# 01-STM32F303VET6.net
KiCad netlist of a schematic drawn in Altium Designer
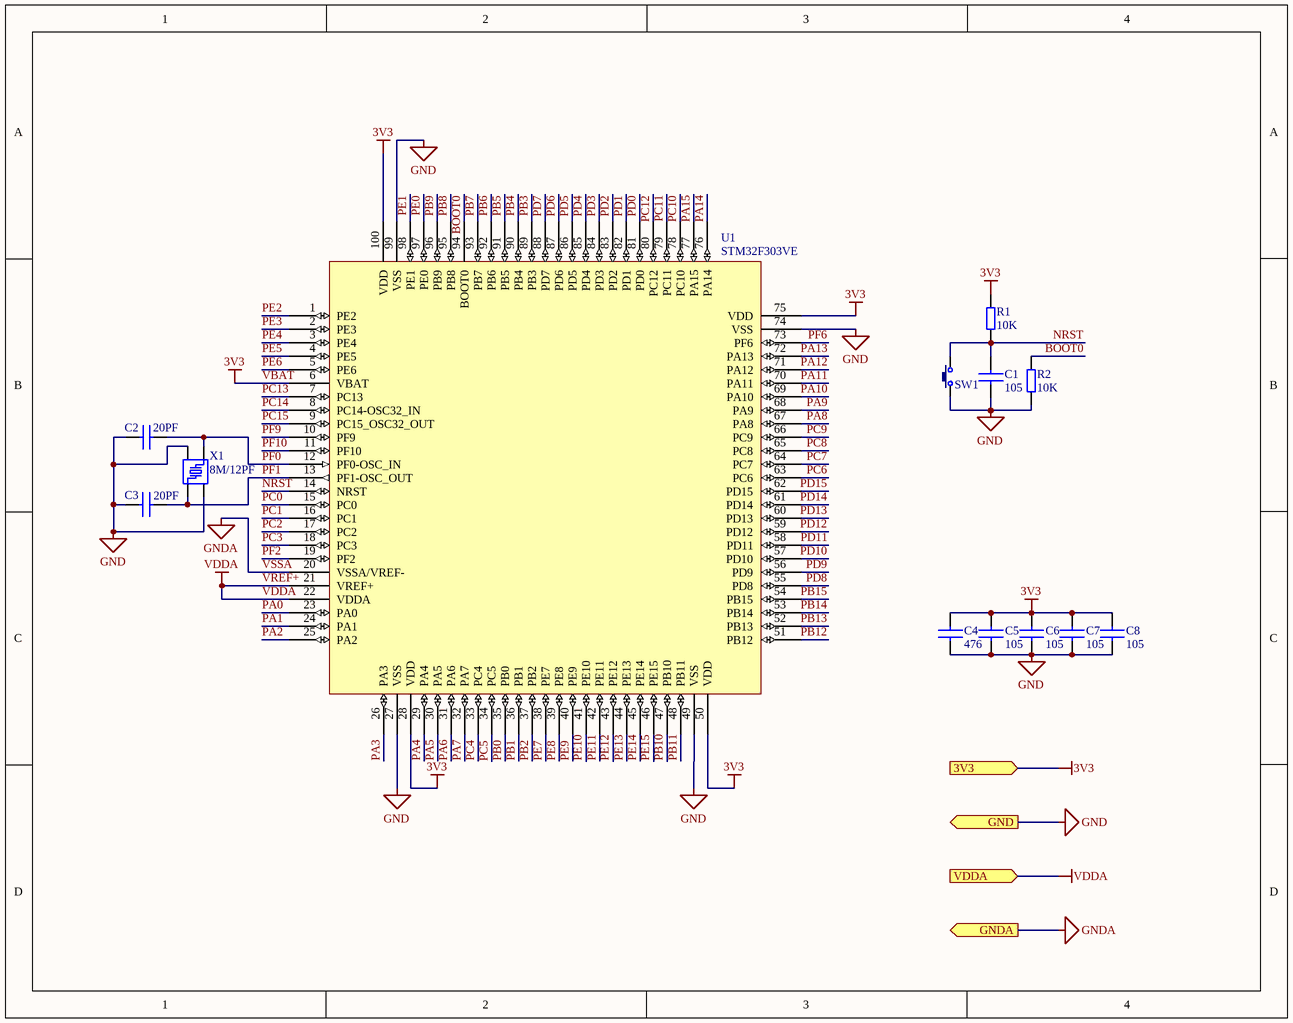
[diagram p0: 01-STM32F303VET6.SchDoc]

(export (version "E")
  (design (tool "Eeschema 10.0.6"))
  (components
    (comp (ref "C1")
      (value "105")
      (footprint "C0603")
      (description "电容")
      (libsource (lib "Schlib1") (part "C"))
    )
    (comp (ref "C2")
      (value "20PF")
      (footprint "C0603")
      (description "电容")
      (libsource (lib "Schlib1") (part "C"))
    )
    (comp (ref "C3")
      (value "20PF")
      (footprint "C0603")
      (description "电容")
      (libsource (lib "Schlib1") (part "C"))
    )
    (comp (ref "C4")
      (value "476")
      (footprint "C0805")
      (description "电容")
      (libsource (lib "Schlib1") (part "C"))
    )
    (comp (ref "C5")
      (value "105")
      (footprint "C0603")
      (description "电容")
      (libsource (lib "Schlib1") (part "C"))
    )
    (comp (ref "C6")
      (value "105")
      (footprint "C0603")
      (description "电容")
      (libsource (lib "Schlib1") (part "C"))
    )
    (comp (ref "C7")
      (value "105")
      (footprint "C0603")
      (description "电容")
      (libsource (lib "Schlib1") (part "C"))
    )
    (comp (ref "C8")
      (value "105")
      (footprint "C0603")
      (description "电容")
      (libsource (lib "Schlib1") (part "C"))
    )
    (comp (ref "R1")
      (value "10K")
      (footprint "R0603")
      (description "电阻")
      (libsource (lib "Schlib1") (part "R"))
    )
    (comp (ref "R2")
      (value "10K")
      (footprint "R0603")
      (description "电阻")
      (libsource (lib "Schlib1") (part "R"))
    )
    (comp (ref "SW1")
      (value "SW3*6*2.5")
      (footprint "SMD-3*6*2.5")
      (description "3*6*2.5轻触开关")
      (fields (field (name "版权归属") "源创客"))
      (libsource (lib "Schlib1") (part "SW3*6*2.5"))
    )
    (comp (ref "U1")
      (value "STM32F303VE")
      (footprint "LQFP-100")
      (description "主控")
      (libsource (lib "Schlib1") (part "STM32F303VE"))
    )
    (comp (ref "X1")
      (value "8M/12PF")
      (footprint "SMD3225-4P")
      (description "晶振")
      (libsource (lib "Schlib1") (part "XTAL"))
    )
  )
  (nets
    (net (code "2") (name "/BOOT0") (class "Default")
      (node (ref "R2") (pin "2") (pinfunction "2_2") (pintype "passive"))
      (node (ref "U1") (pin "94") (pinfunction "BOOT0_94") (pintype "passive"))
    )
    (net (code "3") (name "/NRST") (class "Default")
      (node (ref "C1") (pin "1") (pintype "passive"))
      (node (ref "R1") (pin "1") (pinfunction "1_1") (pintype "passive"))
      (node (ref "SW1") (pin "2") (pinfunction "2_2") (pintype "passive"))
      (node (ref "U1") (pin "14") (pinfunction "NRST_14") (pintype "bidirectional"))
    )
    (net (code "4") (name "/PA0") (class "Default")
      (node (ref "U1") (pin "23") (pinfunction "PA0_23") (pintype "bidirectional"))
    )
    (net (code "5") (name "/PA1") (class "Default")
      (node (ref "U1") (pin "24") (pinfunction "PA1_24") (pintype "bidirectional"))
    )
    (net (code "6") (name "/PA2") (class "Default")
      (node (ref "U1") (pin "25") (pinfunction "PA2_25") (pintype "bidirectional"))
    )
    (net (code "7") (name "/PA3") (class "Default")
      (node (ref "U1") (pin "26") (pinfunction "PA3_26") (pintype "bidirectional"))
    )
    (net (code "8") (name "/PA4") (class "Default")
      (node (ref "U1") (pin "29") (pinfunction "PA4_29") (pintype "bidirectional"))
    )
    (net (code "9") (name "/PA5") (class "Default")
      (node (ref "U1") (pin "30") (pinfunction "PA5_30") (pintype "bidirectional"))
    )
    (net (code "10") (name "/PA6") (class "Default")
      (node (ref "U1") (pin "31") (pinfunction "PA6_31") (pintype "bidirectional"))
    )
    (net (code "11") (name "/PA7") (class "Default")
      (node (ref "U1") (pin "32") (pinfunction "PA7_32") (pintype "bidirectional"))
    )
    (net (code "12") (name "/PA8") (class "Default")
      (node (ref "U1") (pin "67") (pinfunction "PA8_67") (pintype "bidirectional"))
    )
    (net (code "13") (name "/PA9") (class "Default")
      (node (ref "U1") (pin "68") (pinfunction "PA9_68") (pintype "bidirectional"))
    )
    (net (code "14") (name "/PA10") (class "Default")
      (node (ref "U1") (pin "69") (pinfunction "PA10_69") (pintype "bidirectional"))
    )
    (net (code "15") (name "/PA11") (class "Default")
      (node (ref "U1") (pin "70") (pinfunction "PA11_70") (pintype "bidirectional"))
    )
    (net (code "16") (name "/PA12") (class "Default")
      (node (ref "U1") (pin "71") (pinfunction "PA12_71") (pintype "bidirectional"))
    )
    (net (code "17") (name "/PA13") (class "Default")
      (node (ref "U1") (pin "72") (pinfunction "PA13_72") (pintype "bidirectional"))
    )
    (net (code "18") (name "/PA14") (class "Default")
      (node (ref "U1") (pin "76") (pinfunction "PA14_76") (pintype "bidirectional"))
    )
    (net (code "19") (name "/PA15") (class "Default")
      (node (ref "U1") (pin "77") (pinfunction "PA15_77") (pintype "bidirectional"))
    )
    (net (code "20") (name "/PB0") (class "Default")
      (node (ref "U1") (pin "35") (pinfunction "PB0_35") (pintype "bidirectional"))
    )
    (net (code "21") (name "/PB1") (class "Default")
      (node (ref "U1") (pin "36") (pinfunction "PB1_36") (pintype "bidirectional"))
    )
    (net (code "22") (name "/PB2") (class "Default")
      (node (ref "U1") (pin "37") (pinfunction "PB2_37") (pintype "bidirectional"))
    )
    (net (code "23") (name "/PB3") (class "Default")
      (node (ref "U1") (pin "89") (pinfunction "PB3_89") (pintype "bidirectional"))
    )
    (net (code "24") (name "/PB4") (class "Default")
      (node (ref "U1") (pin "90") (pinfunction "PB4_90") (pintype "bidirectional"))
    )
    (net (code "25") (name "/PB5") (class "Default")
      (node (ref "U1") (pin "91") (pinfunction "PB5_91") (pintype "bidirectional"))
    )
    (net (code "26") (name "/PB6") (class "Default")
      (node (ref "U1") (pin "92") (pinfunction "PB6_92") (pintype "bidirectional"))
    )
    (net (code "27") (name "/PB7") (class "Default")
      (node (ref "U1") (pin "93") (pinfunction "PB7_93") (pintype "bidirectional"))
    )
    (net (code "28") (name "/PB8") (class "Default")
      (node (ref "U1") (pin "95") (pinfunction "PB8_95") (pintype "bidirectional"))
    )
    (net (code "29") (name "/PB9") (class "Default")
      (node (ref "U1") (pin "96") (pinfunction "PB9_96") (pintype "bidirectional"))
    )
    (net (code "31") (name "/PB10") (class "Default")
      (node (ref "U1") (pin "47") (pinfunction "PB10_47") (pintype "bidirectional"))
    )
    (net (code "32") (name "/PB11") (class "Default")
      (node (ref "U1") (pin "48") (pinfunction "PB11_48") (pintype "bidirectional"))
    )
    (net (code "33") (name "/PB12") (class "Default")
      (node (ref "U1") (pin "51") (pinfunction "PB12_51") (pintype "bidirectional"))
    )
    (net (code "34") (name "/PB13") (class "Default")
      (node (ref "U1") (pin "52") (pinfunction "PB13_52") (pintype "bidirectional"))
    )
    (net (code "35") (name "/PB14") (class "Default")
      (node (ref "U1") (pin "53") (pinfunction "PB14_53") (pintype "bidirectional"))
    )
    (net (code "36") (name "/PB15") (class "Default")
      (node (ref "U1") (pin "54") (pinfunction "PB15_54") (pintype "bidirectional"))
    )
    (net (code "37") (name "/PC0") (class "Default")
      (node (ref "U1") (pin "15") (pinfunction "PC0_15") (pintype "bidirectional"))
    )
    (net (code "38") (name "/PC1") (class "Default")
      (node (ref "U1") (pin "16") (pinfunction "PC1_16") (pintype "bidirectional"))
    )
    (net (code "39") (name "/PC2") (class "Default")
      (node (ref "U1") (pin "17") (pinfunction "PC2_17") (pintype "bidirectional"))
    )
    (net (code "40") (name "/PC3") (class "Default")
      (node (ref "U1") (pin "18") (pinfunction "PC3_18") (pintype "bidirectional"))
    )
    (net (code "41") (name "/PC4") (class "Default")
      (node (ref "U1") (pin "33") (pinfunction "PC4_33") (pintype "bidirectional"))
    )
    (net (code "42") (name "/PC5") (class "Default")
      (node (ref "U1") (pin "34") (pinfunction "PC5_34") (pintype "bidirectional"))
    )
    (net (code "43") (name "/PC6") (class "Default")
      (node (ref "U1") (pin "63") (pinfunction "PC6_63") (pintype "bidirectional"))
    )
    (net (code "44") (name "/PC7") (class "Default")
      (node (ref "U1") (pin "64") (pinfunction "PC7_64") (pintype "bidirectional"))
    )
    (net (code "45") (name "/PC8") (class "Default")
      (node (ref "U1") (pin "65") (pinfunction "PC8_65") (pintype "bidirectional"))
    )
    (net (code "46") (name "/PC9") (class "Default")
      (node (ref "U1") (pin "66") (pinfunction "PC9_66") (pintype "bidirectional"))
    )
    (net (code "47") (name "/PC10") (class "Default")
      (node (ref "U1") (pin "78") (pinfunction "PC10_78") (pintype "bidirectional"))
    )
    (net (code "48") (name "/PC11") (class "Default")
      (node (ref "U1") (pin "79") (pinfunction "PC11_79") (pintype "bidirectional"))
    )
    (net (code "49") (name "/PC12") (class "Default")
      (node (ref "U1") (pin "80") (pinfunction "PC12_80") (pintype "bidirectional"))
    )
    (net (code "50") (name "/PC13") (class "Default")
      (node (ref "U1") (pin "7") (pinfunction "PC13_7") (pintype "bidirectional"))
    )
    (net (code "51") (name "/PC14") (class "Default")
      (node (ref "U1") (pin "8") (pinfunction "PC14-OSC32_IN_8") (pintype "bidirectional"))
    )
    (net (code "52") (name "/PC15") (class "Default")
      (node (ref "U1") (pin "9") (pinfunction "PC15_OSC32_OUT_9") (pintype "bidirectional"))
    )
    (net (code "53") (name "/PD0") (class "Default")
      (node (ref "U1") (pin "81") (pinfunction "PD0_81") (pintype "bidirectional"))
    )
    (net (code "54") (name "/PD1") (class "Default")
      (node (ref "U1") (pin "82") (pinfunction "PD1_82") (pintype "bidirectional"))
    )
    (net (code "55") (name "/PD2") (class "Default")
      (node (ref "U1") (pin "83") (pinfunction "PD2_83") (pintype "bidirectional"))
    )
    (net (code "56") (name "/PD3") (class "Default")
      (node (ref "U1") (pin "84") (pinfunction "PD3_84") (pintype "bidirectional"))
    )
    (net (code "57") (name "/PD4") (class "Default")
      (node (ref "U1") (pin "85") (pinfunction "PD4_85") (pintype "bidirectional"))
    )
    (net (code "58") (name "/PD5") (class "Default")
      (node (ref "U1") (pin "86") (pinfunction "PD5_86") (pintype "bidirectional"))
    )
    (net (code "59") (name "/PD6") (class "Default")
      (node (ref "U1") (pin "87") (pinfunction "PD6_87") (pintype "bidirectional"))
    )
    (net (code "60") (name "/PD7") (class "Default")
      (node (ref "U1") (pin "88") (pinfunction "PD7_88") (pintype "bidirectional"))
    )
    (net (code "61") (name "/PD8") (class "Default")
      (node (ref "U1") (pin "55") (pinfunction "PD8_55") (pintype "bidirectional"))
    )
    (net (code "62") (name "/PD9") (class "Default")
      (node (ref "U1") (pin "56") (pinfunction "PD9_56") (pintype "bidirectional"))
    )
    (net (code "63") (name "/PD10") (class "Default")
      (node (ref "U1") (pin "57") (pinfunction "PD10_57") (pintype "bidirectional"))
    )
    (net (code "64") (name "/PD11") (class "Default")
      (node (ref "U1") (pin "58") (pinfunction "PD11_58") (pintype "bidirectional"))
    )
    (net (code "65") (name "/PD12") (class "Default")
      (node (ref "U1") (pin "59") (pinfunction "PD12_59") (pintype "bidirectional"))
    )
    (net (code "66") (name "/PD13") (class "Default")
      (node (ref "U1") (pin "60") (pinfunction "PD13_60") (pintype "bidirectional"))
    )
    (net (code "67") (name "/PD14") (class "Default")
      (node (ref "U1") (pin "61") (pinfunction "PD14_61") (pintype "bidirectional"))
    )
    (net (code "68") (name "/PD15") (class "Default")
      (node (ref "U1") (pin "62") (pinfunction "PD15_62") (pintype "bidirectional"))
    )
    (net (code "69") (name "/PE0") (class "Default")
      (node (ref "U1") (pin "97") (pinfunction "PE0_97") (pintype "bidirectional"))
    )
    (net (code "70") (name "/PE1") (class "Default")
      (node (ref "U1") (pin "98") (pinfunction "PE1_98") (pintype "bidirectional"))
    )
    (net (code "71") (name "/PE2") (class "Default")
      (node (ref "U1") (pin "1") (pinfunction "PE2_1") (pintype "bidirectional"))
    )
    (net (code "72") (name "/PE3") (class "Default")
      (node (ref "U1") (pin "2") (pinfunction "PE3_2") (pintype "bidirectional"))
    )
    (net (code "73") (name "/PE4") (class "Default")
      (node (ref "U1") (pin "3") (pinfunction "PE4_3") (pintype "bidirectional"))
    )
    (net (code "74") (name "/PE5") (class "Default")
      (node (ref "U1") (pin "4") (pinfunction "PE5_4") (pintype "bidirectional"))
    )
    (net (code "75") (name "/PE6") (class "Default")
      (node (ref "U1") (pin "5") (pinfunction "PE6_5") (pintype "bidirectional"))
    )
    (net (code "76") (name "/PE7") (class "Default")
      (node (ref "U1") (pin "38") (pinfunction "PE7_38") (pintype "bidirectional"))
    )
    (net (code "77") (name "/PE8") (class "Default")
      (node (ref "U1") (pin "39") (pinfunction "PE8_39") (pintype "bidirectional"))
    )
    (net (code "79") (name "/PE9") (class "Default")
      (node (ref "U1") (pin "40") (pinfunction "PE9_40") (pintype "bidirectional"))
    )
    (net (code "81") (name "/PE10") (class "Default")
      (node (ref "U1") (pin "41") (pinfunction "PE10_41") (pintype "bidirectional"))
    )
    (net (code "82") (name "/PE11") (class "Default")
      (node (ref "U1") (pin "42") (pinfunction "PE11_42") (pintype "bidirectional"))
    )
    (net (code "84") (name "/PE12") (class "Default")
      (node (ref "U1") (pin "43") (pinfunction "PE12_43") (pintype "bidirectional"))
    )
    (net (code "85") (name "/PE13") (class "Default")
      (node (ref "U1") (pin "44") (pinfunction "PE13_44") (pintype "bidirectional"))
    )
    (net (code "86") (name "/PE14") (class "Default")
      (node (ref "U1") (pin "45") (pinfunction "PE14_45") (pintype "bidirectional"))
    )
    (net (code "87") (name "/PE15") (class "Default")
      (node (ref "U1") (pin "46") (pinfunction "PE15_46") (pintype "bidirectional"))
    )
    (net (code "88") (name "/PF0") (class "Default")
      (node (ref "C2") (pin "2") (pintype "passive"))
      (node (ref "U1") (pin "12") (pinfunction "PF0-OSC_IN_12") (pintype "input"))
      (node (ref "X1") (pin "3") (pinfunction "3_3") (pintype "passive"))
    )
    (net (code "89") (name "/PF1") (class "Default")
      (node (ref "C3") (pin "2") (pintype "passive"))
      (node (ref "U1") (pin "13") (pinfunction "PF1-OSC_OUT_13") (pintype "output"))
      (node (ref "X1") (pin "1") (pinfunction "1_1") (pintype "passive"))
    )
    (net (code "90") (name "/PF2") (class "Default")
      (node (ref "U1") (pin "19") (pinfunction "PF2_19") (pintype "bidirectional"))
    )
    (net (code "91") (name "/PF6") (class "Default")
      (node (ref "U1") (pin "73") (pinfunction "PF6_73") (pintype "bidirectional"))
    )
    (net (code "92") (name "/PF9") (class "Default")
      (node (ref "U1") (pin "10") (pinfunction "PF9_10") (pintype "bidirectional"))
    )
    (net (code "93") (name "/PF10") (class "Default")
      (node (ref "U1") (pin "11") (pinfunction "PF10_11") (pintype "bidirectional"))
    )
    (net (code "94") (name "3V3") (class "Default")
      (node (ref "C4") (pin "1") (pintype "passive"))
      (node (ref "C5") (pin "1") (pintype "passive"))
      (node (ref "C6") (pin "1") (pintype "passive"))
      (node (ref "C7") (pin "1") (pintype "passive"))
      (node (ref "C8") (pin "1") (pintype "passive"))
      (node (ref "R1") (pin "2") (pinfunction "2_2") (pintype "passive"))
      (node (ref "U1") (pin "100") (pinfunction "VDD_100") (pintype "power_in"))
      (node (ref "U1") (pin "28") (pinfunction "VDD_28") (pintype "power_in"))
      (node (ref "U1") (pin "50") (pinfunction "VDD_50") (pintype "power_in"))
      (node (ref "U1") (pin "6") (pinfunction "VBAT_6") (pintype "power_in"))
      (node (ref "U1") (pin "75") (pinfunction "VDD_75") (pintype "power_in"))
    )
    (net (code "95") (name "GND") (class "Default")
      (node (ref "C1") (pin "2") (pintype "passive"))
      (node (ref "C2") (pin "1") (pintype "passive"))
      (node (ref "C3") (pin "1") (pintype "passive"))
      (node (ref "C4") (pin "2") (pintype "passive"))
      (node (ref "C5") (pin "2") (pintype "passive"))
      (node (ref "C6") (pin "2") (pintype "passive"))
      (node (ref "C7") (pin "2") (pintype "passive"))
      (node (ref "C8") (pin "2") (pintype "passive"))
      (node (ref "R2") (pin "1") (pinfunction "1_1") (pintype "passive"))
      (node (ref "SW1") (pin "1") (pinfunction "1_1") (pintype "passive"))
      (node (ref "U1") (pin "27") (pinfunction "VSS_27") (pintype "power_in"))
      (node (ref "U1") (pin "49") (pinfunction "VSS_49") (pintype "power_in"))
      (node (ref "U1") (pin "74") (pinfunction "VSS_74") (pintype "power_in"))
      (node (ref "U1") (pin "99") (pinfunction "VSS_99") (pintype "power_in"))
      (node (ref "X1") (pin "2") (pinfunction "2_2") (pintype "passive"))
      (node (ref "X1") (pin "4") (pinfunction "4_4") (pintype "passive"))
    )
    (net (code "96") (name "GNDA") (class "Default")
      (node (ref "U1") (pin "20") (pinfunction "VSSA/VREF-_20") (pintype "power_in"))
    )
    (net (code "97") (name "VDDA") (class "Default")
      (node (ref "U1") (pin "21") (pinfunction "VREF+_21") (pintype "power_in"))
      (node (ref "U1") (pin "22") (pinfunction "VDDA_22") (pintype "power_in"))
    )
  )
)
